# Mega2560_Grbl_to_RAMPS1-4_driver.net
KiCad netlist of a schematic drawn in EAGLE
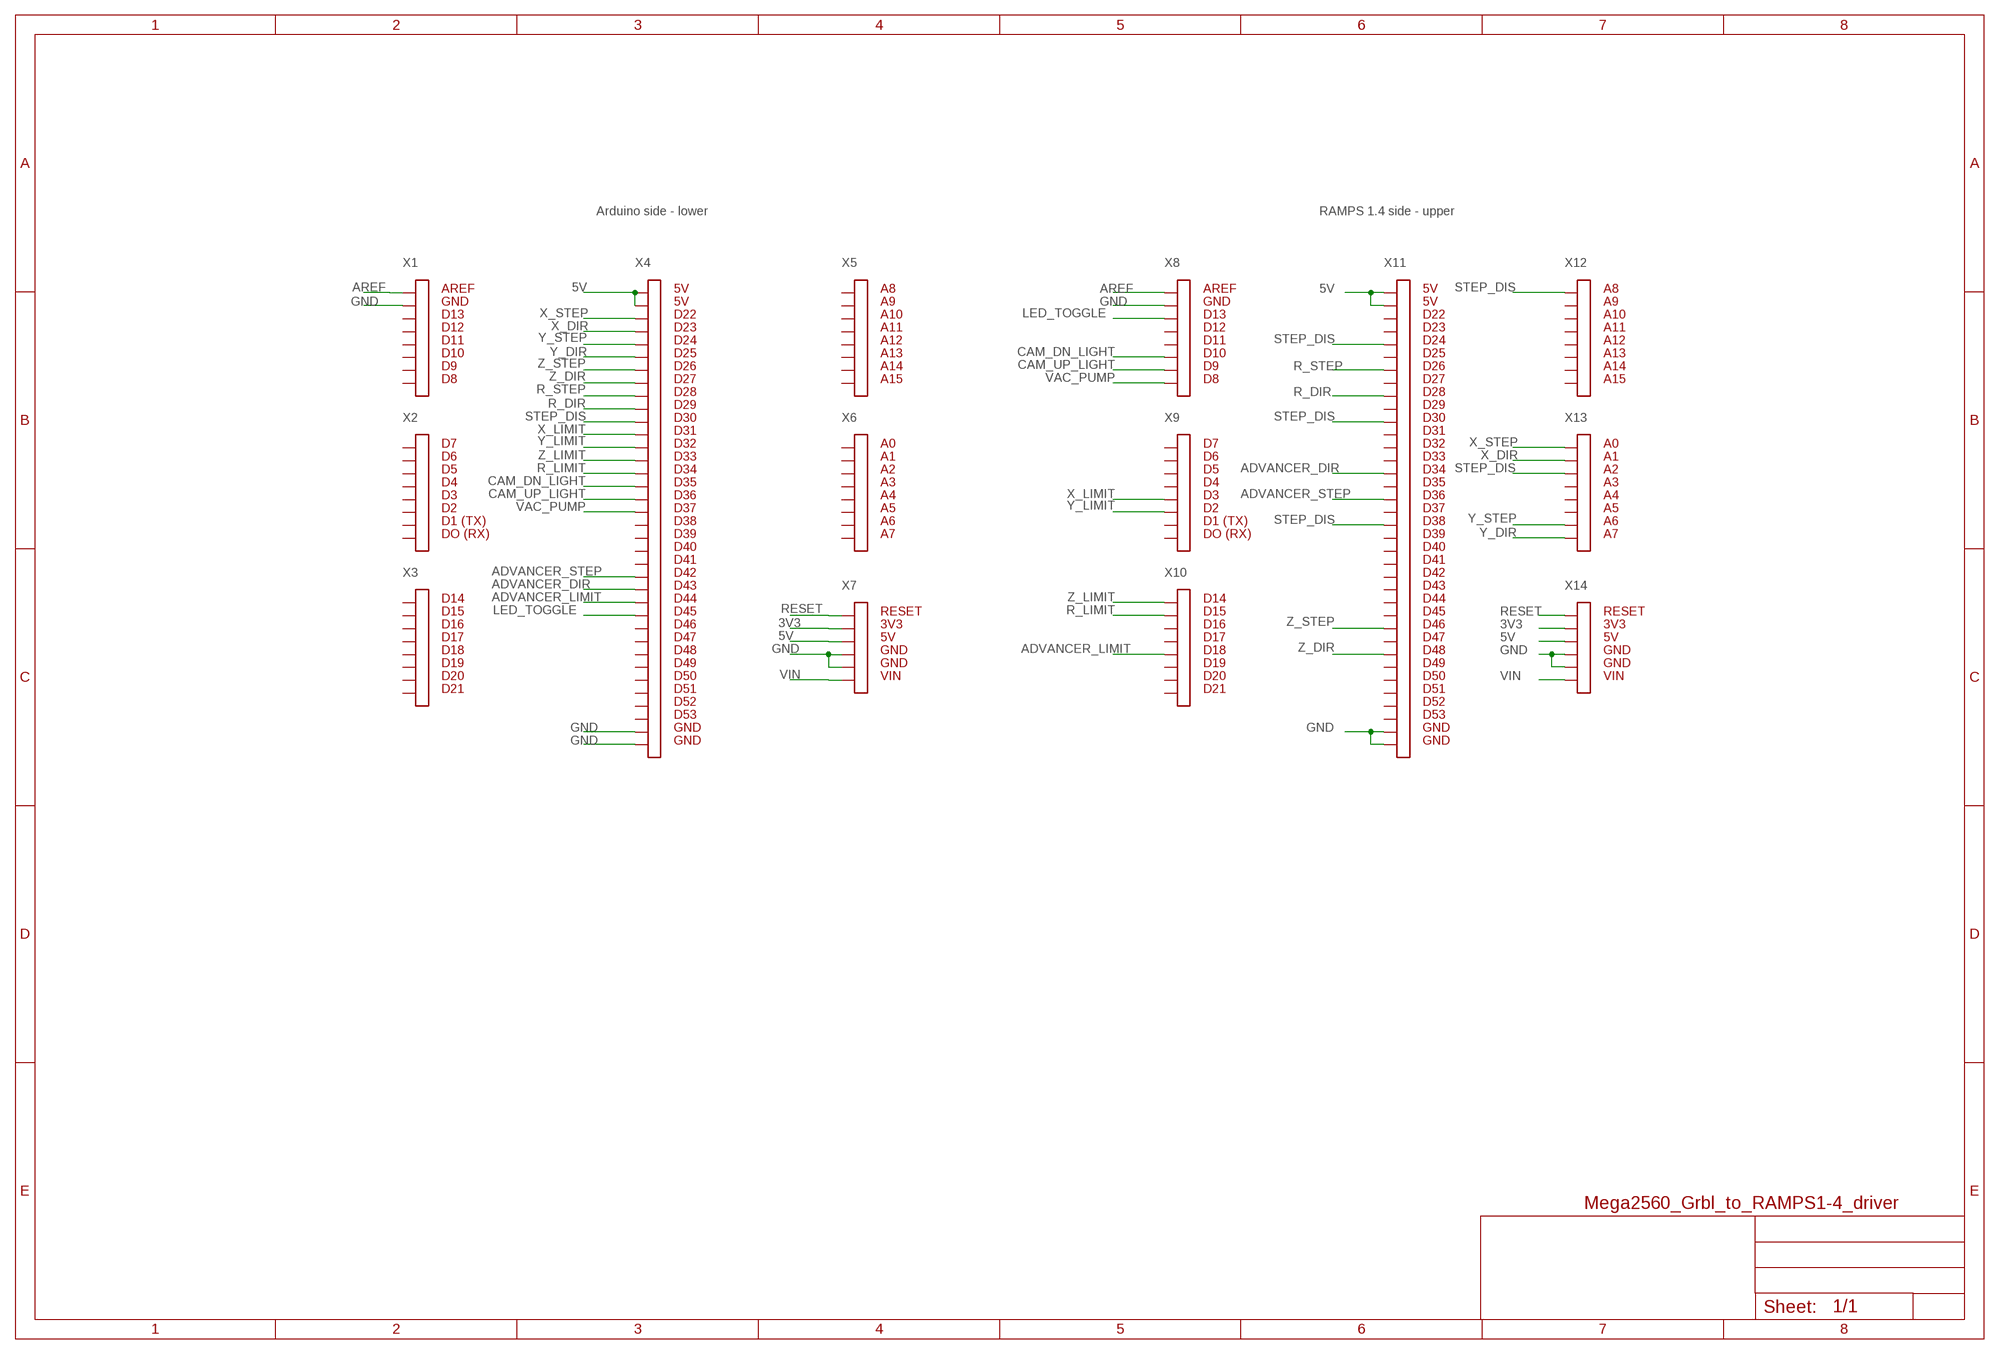
[diagram p0: schematic, sheet 1]

(export (version "E")
  (design (tool "Eeschema 10.0.6"))
  (components
    (comp (ref "X1")
      (value "M20-9770842")
      (footprint "eagle-import:8X1-P2.54-D1.00")
      (libsource (lib "eagle-import") (part "M20-9770842"))
    )
    (comp (ref "X2")
      (value "M20-9770842")
      (footprint "eagle-import:8X1-P2.54-D1.00")
      (libsource (lib "eagle-import") (part "M20-9770842"))
    )
    (comp (ref "X3")
      (value "M20-9770842")
      (footprint "eagle-import:8X1-P2.54-D1.00")
      (libsource (lib "eagle-import") (part "M20-9770842"))
    )
    (comp (ref "X4")
      (value "M20-9761842FLIP")
      (footprint "eagle-import:18X2-P2.54-D1.00")
      (libsource (lib "eagle-import") (part "M20-9761842FLIP"))
    )
    (comp (ref "X5")
      (value "M20-9770842")
      (footprint "eagle-import:8X1-P2.54-D1.00")
      (libsource (lib "eagle-import") (part "M20-9770842"))
    )
    (comp (ref "X6")
      (value "M20-9770842")
      (footprint "eagle-import:8X1-P2.54-D1.00")
      (libsource (lib "eagle-import") (part "M20-9770842"))
    )
    (comp (ref "X7")
      (value "M20-9770642")
      (footprint "eagle-import:6X1-P2.54-D1.00")
      (libsource (lib "eagle-import") (part "M20-9770642"))
    )
    (comp (ref "X8")
      (value "M20-7820842")
      (footprint "eagle-import:8X1-P2.54-D1.00")
      (libsource (lib "eagle-import") (part "M20-7820842"))
    )
    (comp (ref "X9")
      (value "M20-7820842")
      (footprint "eagle-import:8X1-P2.54-D1.00")
      (libsource (lib "eagle-import") (part "M20-7820842"))
    )
    (comp (ref "X10")
      (value "M20-7820842")
      (footprint "eagle-import:8X1-P2.54-D1.00")
      (libsource (lib "eagle-import") (part "M20-7820842"))
    )
    (comp (ref "X11")
      (value "M20-7831842")
      (footprint "eagle-import:18X2-P2.54-D1.00")
      (libsource (lib "eagle-import") (part "M20-7831842"))
    )
    (comp (ref "X12")
      (value "M20-7820842")
      (footprint "eagle-import:8X1-P2.54-D1.00")
      (libsource (lib "eagle-import") (part "M20-7820842"))
    )
    (comp (ref "X13")
      (value "M20-7820842")
      (footprint "eagle-import:8X1-P2.54-D1.00")
      (libsource (lib "eagle-import") (part "M20-7820842"))
    )
    (comp (ref "X14")
      (value "M20-7820642")
      (footprint "eagle-import:6X1-P2.54-D1.00")
      (libsource (lib "eagle-import") (part "M20-7820642"))
    )
  )
  (nets
    (net (code "1") (name "/3V3") (class "Default")
      (node (ref "X14") (pin "P$2") (pinfunction "P$2_P$2") (pintype "passive"))
      (node (ref "X7") (pin "P$2") (pinfunction "P$2_P$2") (pintype "passive"))
    )
    (net (code "2") (name "/5V") (class "Default")
      (node (ref "X11") (pin "P$1") (pinfunction "P$1_P$1") (pintype "passive"))
      (node (ref "X11") (pin "P$2") (pinfunction "P$2_P$2") (pintype "passive"))
      (node (ref "X14") (pin "P$3") (pinfunction "P$3_P$3") (pintype "passive"))
      (node (ref "X4") (pin "P$1") (pinfunction "P$2_P$1") (pintype "passive"))
      (node (ref "X4") (pin "P$2") (pinfunction "P$1_P$2") (pintype "passive"))
      (node (ref "X7") (pin "P$3") (pinfunction "P$3_P$3") (pintype "passive"))
    )
    (net (code "3") (name "/ADVANCER_DIR") (class "Default")
      (node (ref "X11") (pin "P$15") (pinfunction "P$15_P$15") (pintype "passive"))
      (node (ref "X4") (pin "P$23") (pinfunction "P$24_P$23") (pintype "passive"))
    )
    (net (code "4") (name "/ADVANCER_LIMIT") (class "Default")
      (node (ref "X10") (pin "P$5") (pinfunction "P$5_P$5") (pintype "passive"))
      (node (ref "X4") (pin "P$26") (pinfunction "P$25_P$26") (pintype "passive"))
    )
    (net (code "5") (name "/ADVANCER_STEP") (class "Default")
      (node (ref "X11") (pin "P$17") (pinfunction "P$17_P$17") (pintype "passive"))
      (node (ref "X4") (pin "P$24") (pinfunction "P$23_P$24") (pintype "passive"))
    )
    (net (code "6") (name "/AREF") (class "Default")
      (node (ref "X1") (pin "P$1") (pinfunction "P$1_P$1") (pintype "passive"))
      (node (ref "X8") (pin "P$1") (pinfunction "P$1_P$1") (pintype "passive"))
    )
    (net (code "7") (name "/CAM_DN_LIGHT") (class "Default")
      (node (ref "X4") (pin "P$15") (pinfunction "P$16_P$15") (pintype "passive"))
      (node (ref "X8") (pin "P$6") (pinfunction "P$6_P$6") (pintype "passive"))
    )
    (net (code "8") (name "/CAM_UP_LIGHT") (class "Default")
      (node (ref "X4") (pin "P$18") (pinfunction "P$17_P$18") (pintype "passive"))
      (node (ref "X8") (pin "P$7") (pinfunction "P$7_P$7") (pintype "passive"))
    )
    (net (code "9") (name "/GND") (class "Default")
      (node (ref "X1") (pin "P$2") (pinfunction "P$2_P$2") (pintype "passive"))
      (node (ref "X11") (pin "P$35") (pinfunction "P$35_P$35") (pintype "passive"))
      (node (ref "X11") (pin "P$36") (pinfunction "P$36_P$36") (pintype "passive"))
      (node (ref "X14") (pin "P$4") (pinfunction "P$4_P$4") (pintype "passive"))
      (node (ref "X14") (pin "P$5") (pinfunction "P$5_P$5") (pintype "passive"))
      (node (ref "X4") (pin "P$35") (pinfunction "P$36_P$35") (pintype "passive"))
      (node (ref "X4") (pin "P$36") (pinfunction "P$35_P$36") (pintype "passive"))
      (node (ref "X7") (pin "P$4") (pinfunction "P$4_P$4") (pintype "passive"))
      (node (ref "X7") (pin "P$5") (pinfunction "P$5_P$5") (pintype "passive"))
      (node (ref "X8") (pin "P$2") (pinfunction "P$2_P$2") (pintype "passive"))
    )
    (net (code "10") (name "/LED_TOGGLE") (class "Default")
      (node (ref "X4") (pin "P$25") (pinfunction "P$26_P$25") (pintype "passive"))
      (node (ref "X8") (pin "P$3") (pinfunction "P$3_P$3") (pintype "passive"))
    )
    (net (code "11") (name "/RESET") (class "Default")
      (node (ref "X14") (pin "P$1") (pinfunction "P$1_P$1") (pintype "passive"))
      (node (ref "X7") (pin "P$1") (pinfunction "P$1_P$1") (pintype "passive"))
    )
    (net (code "12") (name "/R_DIR") (class "Default")
      (node (ref "X11") (pin "P$9") (pinfunction "P$9_P$9") (pintype "passive"))
      (node (ref "X4") (pin "P$9") (pinfunction "P$10_P$9") (pintype "passive"))
    )
    (net (code "13") (name "/R_LIMIT") (class "Default")
      (node (ref "X10") (pin "P$2") (pinfunction "P$2_P$2") (pintype "passive"))
      (node (ref "X4") (pin "P$16") (pinfunction "P$15_P$16") (pintype "passive"))
    )
    (net (code "14") (name "/R_STEP") (class "Default")
      (node (ref "X11") (pin "P$7") (pinfunction "P$7_P$7") (pintype "passive"))
      (node (ref "X4") (pin "P$10") (pinfunction "P$9_P$10") (pintype "passive"))
    )
    (net (code "15") (name "/STEP_DIS") (class "Default")
      (node (ref "X11") (pin "P$11") (pinfunction "P$11_P$11") (pintype "passive"))
      (node (ref "X11") (pin "P$19") (pinfunction "P$19_P$19") (pintype "passive"))
      (node (ref "X11") (pin "P$5") (pinfunction "P$5_P$5") (pintype "passive"))
      (node (ref "X12") (pin "P$1") (pinfunction "P$1_P$1") (pintype "passive"))
      (node (ref "X13") (pin "P$3") (pinfunction "P$3_P$3") (pintype "passive"))
      (node (ref "X4") (pin "P$12") (pinfunction "P$11_P$12") (pintype "passive"))
    )
    (net (code "16") (name "/VAC_PUMP") (class "Default")
      (node (ref "X4") (pin "P$17") (pinfunction "P$18_P$17") (pintype "passive"))
      (node (ref "X8") (pin "P$8") (pinfunction "P$8_P$8") (pintype "passive"))
    )
    (net (code "17") (name "/VIN") (class "Default")
      (node (ref "X14") (pin "P$6") (pinfunction "P$6_P$6") (pintype "passive"))
      (node (ref "X7") (pin "P$6") (pinfunction "P$6_P$6") (pintype "passive"))
    )
    (net (code "18") (name "/X_DIR") (class "Default")
      (node (ref "X13") (pin "P$2") (pinfunction "P$2_P$2") (pintype "passive"))
      (node (ref "X4") (pin "P$3") (pinfunction "P$4_P$3") (pintype "passive"))
    )
    (net (code "19") (name "/X_LIMIT") (class "Default")
      (node (ref "X4") (pin "P$11") (pinfunction "P$12_P$11") (pintype "passive"))
      (node (ref "X9") (pin "P$5") (pinfunction "P$5_P$5") (pintype "passive"))
    )
    (net (code "20") (name "/X_STEP") (class "Default")
      (node (ref "X13") (pin "P$1") (pinfunction "P$1_P$1") (pintype "passive"))
      (node (ref "X4") (pin "P$4") (pinfunction "P$3_P$4") (pintype "passive"))
    )
    (net (code "21") (name "/Y_DIR") (class "Default")
      (node (ref "X13") (pin "P$8") (pinfunction "P$8_P$8") (pintype "passive"))
      (node (ref "X4") (pin "P$5") (pinfunction "P$6_P$5") (pintype "passive"))
    )
    (net (code "22") (name "/Y_LIMIT") (class "Default")
      (node (ref "X4") (pin "P$14") (pinfunction "P$13_P$14") (pintype "passive"))
      (node (ref "X9") (pin "P$6") (pinfunction "P$6_P$6") (pintype "passive"))
    )
    (net (code "23") (name "/Y_STEP") (class "Default")
      (node (ref "X13") (pin "P$7") (pinfunction "P$7_P$7") (pintype "passive"))
      (node (ref "X4") (pin "P$6") (pinfunction "P$5_P$6") (pintype "passive"))
    )
    (net (code "24") (name "/Z_DIR") (class "Default")
      (node (ref "X11") (pin "P$29") (pinfunction "P$29_P$29") (pintype "passive"))
      (node (ref "X4") (pin "P$7") (pinfunction "P$8_P$7") (pintype "passive"))
    )
    (net (code "25") (name "/Z_LIMIT") (class "Default")
      (node (ref "X10") (pin "P$1") (pinfunction "P$1_P$1") (pintype "passive"))
      (node (ref "X4") (pin "P$13") (pinfunction "P$14_P$13") (pintype "passive"))
    )
    (net (code "26") (name "/Z_STEP") (class "Default")
      (node (ref "X11") (pin "P$27") (pinfunction "P$27_P$27") (pintype "passive"))
      (node (ref "X4") (pin "P$8") (pinfunction "P$7_P$8") (pintype "passive"))
    )
    (net (code "27") (name "unconnected-(X1-PadP$3)") (class "Default")
      (node (ref "X1") (pin "P$3") (pinfunction "P$3_P$3") (pintype "passive"))
    )
    (net (code "28") (name "unconnected-(X1-PadP$4)") (class "Default")
      (node (ref "X1") (pin "P$4") (pinfunction "P$4_P$4") (pintype "passive"))
    )
    (net (code "29") (name "unconnected-(X1-PadP$5)") (class "Default")
      (node (ref "X1") (pin "P$5") (pinfunction "P$5_P$5") (pintype "passive"))
    )
    (net (code "30") (name "unconnected-(X1-PadP$6)") (class "Default")
      (node (ref "X1") (pin "P$6") (pinfunction "P$6_P$6") (pintype "passive"))
    )
    (net (code "31") (name "unconnected-(X1-PadP$7)") (class "Default")
      (node (ref "X1") (pin "P$7") (pinfunction "P$7_P$7") (pintype "passive"))
    )
    (net (code "32") (name "unconnected-(X1-PadP$8)") (class "Default")
      (node (ref "X1") (pin "P$8") (pinfunction "P$8_P$8") (pintype "passive"))
    )
    (net (code "33") (name "unconnected-(X2-PadP$1)") (class "Default")
      (node (ref "X2") (pin "P$1") (pinfunction "P$1_P$1") (pintype "passive"))
    )
    (net (code "34") (name "unconnected-(X2-PadP$2)") (class "Default")
      (node (ref "X2") (pin "P$2") (pinfunction "P$2_P$2") (pintype "passive"))
    )
    (net (code "35") (name "unconnected-(X2-PadP$3)") (class "Default")
      (node (ref "X2") (pin "P$3") (pinfunction "P$3_P$3") (pintype "passive"))
    )
    (net (code "36") (name "unconnected-(X2-PadP$4)") (class "Default")
      (node (ref "X2") (pin "P$4") (pinfunction "P$4_P$4") (pintype "passive"))
    )
    (net (code "37") (name "unconnected-(X2-PadP$5)") (class "Default")
      (node (ref "X2") (pin "P$5") (pinfunction "P$5_P$5") (pintype "passive"))
    )
    (net (code "38") (name "unconnected-(X2-PadP$6)") (class "Default")
      (node (ref "X2") (pin "P$6") (pinfunction "P$6_P$6") (pintype "passive"))
    )
    (net (code "39") (name "unconnected-(X2-PadP$7)") (class "Default")
      (node (ref "X2") (pin "P$7") (pinfunction "P$7_P$7") (pintype "passive"))
    )
    (net (code "40") (name "unconnected-(X2-PadP$8)") (class "Default")
      (node (ref "X2") (pin "P$8") (pinfunction "P$8_P$8") (pintype "passive"))
    )
    (net (code "41") (name "unconnected-(X3-PadP$1)") (class "Default")
      (node (ref "X3") (pin "P$1") (pinfunction "P$1_P$1") (pintype "passive"))
    )
    (net (code "42") (name "unconnected-(X3-PadP$2)") (class "Default")
      (node (ref "X3") (pin "P$2") (pinfunction "P$2_P$2") (pintype "passive"))
    )
    (net (code "43") (name "unconnected-(X3-PadP$3)") (class "Default")
      (node (ref "X3") (pin "P$3") (pinfunction "P$3_P$3") (pintype "passive"))
    )
    (net (code "44") (name "unconnected-(X3-PadP$4)") (class "Default")
      (node (ref "X3") (pin "P$4") (pinfunction "P$4_P$4") (pintype "passive"))
    )
    (net (code "45") (name "unconnected-(X3-PadP$5)") (class "Default")
      (node (ref "X3") (pin "P$5") (pinfunction "P$5_P$5") (pintype "passive"))
    )
    (net (code "46") (name "unconnected-(X3-PadP$6)") (class "Default")
      (node (ref "X3") (pin "P$6") (pinfunction "P$6_P$6") (pintype "passive"))
    )
    (net (code "47") (name "unconnected-(X3-PadP$7)") (class "Default")
      (node (ref "X3") (pin "P$7") (pinfunction "P$7_P$7") (pintype "passive"))
    )
    (net (code "48") (name "unconnected-(X3-PadP$8)") (class "Default")
      (node (ref "X3") (pin "P$8") (pinfunction "P$8_P$8") (pintype "passive"))
    )
    (net (code "49") (name "unconnected-(X4-P$19-PadP$20)") (class "Default")
      (node (ref "X4") (pin "P$20") (pinfunction "P$19_P$20") (pintype "passive"))
    )
    (net (code "50") (name "unconnected-(X4-P$20-PadP$19)") (class "Default")
      (node (ref "X4") (pin "P$19") (pinfunction "P$20_P$19") (pintype "passive"))
    )
    (net (code "51") (name "unconnected-(X4-P$21-PadP$22)") (class "Default")
      (node (ref "X4") (pin "P$22") (pinfunction "P$21_P$22") (pintype "passive"))
    )
    (net (code "52") (name "unconnected-(X4-P$22-PadP$21)") (class "Default")
      (node (ref "X4") (pin "P$21") (pinfunction "P$22_P$21") (pintype "passive"))
    )
    (net (code "53") (name "unconnected-(X4-P$27-PadP$28)") (class "Default")
      (node (ref "X4") (pin "P$28") (pinfunction "P$27_P$28") (pintype "passive"))
    )
    (net (code "54") (name "unconnected-(X4-P$28-PadP$27)") (class "Default")
      (node (ref "X4") (pin "P$27") (pinfunction "P$28_P$27") (pintype "passive"))
    )
    (net (code "55") (name "unconnected-(X4-P$29-PadP$30)") (class "Default")
      (node (ref "X4") (pin "P$30") (pinfunction "P$29_P$30") (pintype "passive"))
    )
    (net (code "56") (name "unconnected-(X4-P$30-PadP$29)") (class "Default")
      (node (ref "X4") (pin "P$29") (pinfunction "P$30_P$29") (pintype "passive"))
    )
    (net (code "57") (name "unconnected-(X4-P$31-PadP$32)") (class "Default")
      (node (ref "X4") (pin "P$32") (pinfunction "P$31_P$32") (pintype "passive"))
    )
    (net (code "58") (name "unconnected-(X4-P$32-PadP$31)") (class "Default")
      (node (ref "X4") (pin "P$31") (pinfunction "P$32_P$31") (pintype "passive"))
    )
    (net (code "59") (name "unconnected-(X4-P$33-PadP$34)") (class "Default")
      (node (ref "X4") (pin "P$34") (pinfunction "P$33_P$34") (pintype "passive"))
    )
    (net (code "60") (name "unconnected-(X4-P$34-PadP$33)") (class "Default")
      (node (ref "X4") (pin "P$33") (pinfunction "P$34_P$33") (pintype "passive"))
    )
    (net (code "61") (name "unconnected-(X5-PadP$1)") (class "Default")
      (node (ref "X5") (pin "P$1") (pinfunction "P$1_P$1") (pintype "passive"))
    )
    (net (code "62") (name "unconnected-(X5-PadP$2)") (class "Default")
      (node (ref "X5") (pin "P$2") (pinfunction "P$2_P$2") (pintype "passive"))
    )
    (net (code "63") (name "unconnected-(X5-PadP$3)") (class "Default")
      (node (ref "X5") (pin "P$3") (pinfunction "P$3_P$3") (pintype "passive"))
    )
    (net (code "64") (name "unconnected-(X5-PadP$4)") (class "Default")
      (node (ref "X5") (pin "P$4") (pinfunction "P$4_P$4") (pintype "passive"))
    )
    (net (code "65") (name "unconnected-(X5-PadP$5)") (class "Default")
      (node (ref "X5") (pin "P$5") (pinfunction "P$5_P$5") (pintype "passive"))
    )
    (net (code "66") (name "unconnected-(X5-PadP$6)") (class "Default")
      (node (ref "X5") (pin "P$6") (pinfunction "P$6_P$6") (pintype "passive"))
    )
    (net (code "67") (name "unconnected-(X5-PadP$7)") (class "Default")
      (node (ref "X5") (pin "P$7") (pinfunction "P$7_P$7") (pintype "passive"))
    )
    (net (code "68") (name "unconnected-(X5-PadP$8)") (class "Default")
      (node (ref "X5") (pin "P$8") (pinfunction "P$8_P$8") (pintype "passive"))
    )
    (net (code "69") (name "unconnected-(X6-PadP$1)") (class "Default")
      (node (ref "X6") (pin "P$1") (pinfunction "P$1_P$1") (pintype "passive"))
    )
    (net (code "70") (name "unconnected-(X6-PadP$2)") (class "Default")
      (node (ref "X6") (pin "P$2") (pinfunction "P$2_P$2") (pintype "passive"))
    )
    (net (code "71") (name "unconnected-(X6-PadP$3)") (class "Default")
      (node (ref "X6") (pin "P$3") (pinfunction "P$3_P$3") (pintype "passive"))
    )
    (net (code "72") (name "unconnected-(X6-PadP$4)") (class "Default")
      (node (ref "X6") (pin "P$4") (pinfunction "P$4_P$4") (pintype "passive"))
    )
    (net (code "73") (name "unconnected-(X6-PadP$5)") (class "Default")
      (node (ref "X6") (pin "P$5") (pinfunction "P$5_P$5") (pintype "passive"))
    )
    (net (code "74") (name "unconnected-(X6-PadP$6)") (class "Default")
      (node (ref "X6") (pin "P$6") (pinfunction "P$6_P$6") (pintype "passive"))
    )
    (net (code "75") (name "unconnected-(X6-PadP$7)") (class "Default")
      (node (ref "X6") (pin "P$7") (pinfunction "P$7_P$7") (pintype "passive"))
    )
    (net (code "76") (name "unconnected-(X6-PadP$8)") (class "Default")
      (node (ref "X6") (pin "P$8") (pinfunction "P$8_P$8") (pintype "passive"))
    )
    (net (code "77") (name "unconnected-(X8-PadP$4)") (class "Default")
      (node (ref "X8") (pin "P$4") (pinfunction "P$4_P$4") (pintype "passive"))
    )
    (net (code "78") (name "unconnected-(X8-PadP$5)") (class "Default")
      (node (ref "X8") (pin "P$5") (pinfunction "P$5_P$5") (pintype "passive"))
    )
    (net (code "79") (name "unconnected-(X9-PadP$1)") (class "Default")
      (node (ref "X9") (pin "P$1") (pinfunction "P$1_P$1") (pintype "passive"))
    )
    (net (code "80") (name "unconnected-(X9-PadP$2)") (class "Default")
      (node (ref "X9") (pin "P$2") (pinfunction "P$2_P$2") (pintype "passive"))
    )
    (net (code "81") (name "unconnected-(X9-PadP$3)") (class "Default")
      (node (ref "X9") (pin "P$3") (pinfunction "P$3_P$3") (pintype "passive"))
    )
    (net (code "82") (name "unconnected-(X9-PadP$4)") (class "Default")
      (node (ref "X9") (pin "P$4") (pinfunction "P$4_P$4") (pintype "passive"))
    )
    (net (code "83") (name "unconnected-(X9-PadP$7)") (class "Default")
      (node (ref "X9") (pin "P$7") (pinfunction "P$7_P$7") (pintype "passive"))
    )
    (net (code "84") (name "unconnected-(X9-PadP$8)") (class "Default")
      (node (ref "X9") (pin "P$8") (pinfunction "P$8_P$8") (pintype "passive"))
    )
    (net (code "85") (name "unconnected-(X10-PadP$3)") (class "Default")
      (node (ref "X10") (pin "P$3") (pinfunction "P$3_P$3") (pintype "passive"))
    )
    (net (code "86") (name "unconnected-(X10-PadP$4)") (class "Default")
      (node (ref "X10") (pin "P$4") (pinfunction "P$4_P$4") (pintype "passive"))
    )
    (net (code "87") (name "unconnected-(X10-PadP$6)") (class "Default")
      (node (ref "X10") (pin "P$6") (pinfunction "P$6_P$6") (pintype "passive"))
    )
    (net (code "88") (name "unconnected-(X10-PadP$7)") (class "Default")
      (node (ref "X10") (pin "P$7") (pinfunction "P$7_P$7") (pintype "passive"))
    )
    (net (code "89") (name "unconnected-(X10-PadP$8)") (class "Default")
      (node (ref "X10") (pin "P$8") (pinfunction "P$8_P$8") (pintype "passive"))
    )
    (net (code "90") (name "unconnected-(X11-PadP$3)") (class "Default")
      (node (ref "X11") (pin "P$3") (pinfunction "P$3_P$3") (pintype "passive"))
    )
    (net (code "91") (name "unconnected-(X11-PadP$4)") (class "Default")
      (node (ref "X11") (pin "P$4") (pinfunction "P$4_P$4") (pintype "passive"))
    )
    (net (code "92") (name "unconnected-(X11-PadP$6)") (class "Default")
      (node (ref "X11") (pin "P$6") (pinfunction "P$6_P$6") (pintype "passive"))
    )
    (net (code "93") (name "unconnected-(X11-PadP$8)") (class "Default")
      (node (ref "X11") (pin "P$8") (pinfunction "P$8_P$8") (pintype "passive"))
    )
    (net (code "94") (name "unconnected-(X11-PadP$10)") (class "Default")
      (node (ref "X11") (pin "P$10") (pinfunction "P$10_P$10") (pintype "passive"))
    )
    (net (code "95") (name "unconnected-(X11-PadP$12)") (class "Default")
      (node (ref "X11") (pin "P$12") (pinfunction "P$12_P$12") (pintype "passive"))
    )
    (net (code "96") (name "unconnected-(X11-PadP$13)") (class "Default")
      (node (ref "X11") (pin "P$13") (pinfunction "P$13_P$13") (pintype "passive"))
    )
    (net (code "97") (name "unconnected-(X11-PadP$14)") (class "Default")
      (node (ref "X11") (pin "P$14") (pinfunction "P$14_P$14") (pintype "passive"))
    )
    (net (code "98") (name "unconnected-(X11-PadP$16)") (class "Default")
      (node (ref "X11") (pin "P$16") (pinfunction "P$16_P$16") (pintype "passive"))
    )
    (net (code "99") (name "unconnected-(X11-PadP$18)") (class "Default")
      (node (ref "X11") (pin "P$18") (pinfunction "P$18_P$18") (pintype "passive"))
    )
    (net (code "100") (name "unconnected-(X11-PadP$20)") (class "Default")
      (node (ref "X11") (pin "P$20") (pinfunction "P$20_P$20") (pintype "passive"))
    )
    (net (code "101") (name "unconnected-(X11-PadP$21)") (class "Default")
      (node (ref "X11") (pin "P$21") (pinfunction "P$21_P$21") (pintype "passive"))
    )
    (net (code "102") (name "unconnected-(X11-PadP$22)") (class "Default")
      (node (ref "X11") (pin "P$22") (pinfunction "P$22_P$22") (pintype "passive"))
    )
    (net (code "103") (name "unconnected-(X11-PadP$23)") (class "Default")
      (node (ref "X11") (pin "P$23") (pinfunction "P$23_P$23") (pintype "passive"))
    )
    (net (code "104") (name "unconnected-(X11-PadP$24)") (class "Default")
      (node (ref "X11") (pin "P$24") (pinfunction "P$24_P$24") (pintype "passive"))
    )
    (net (code "105") (name "unconnected-(X11-PadP$25)") (class "Default")
      (node (ref "X11") (pin "P$25") (pinfunction "P$25_P$25") (pintype "passive"))
    )
    (net (code "106") (name "unconnected-(X11-PadP$26)") (class "Default")
      (node (ref "X11") (pin "P$26") (pinfunction "P$26_P$26") (pintype "passive"))
    )
    (net (code "107") (name "unconnected-(X11-PadP$28)") (class "Default")
      (node (ref "X11") (pin "P$28") (pinfunction "P$28_P$28") (pintype "passive"))
    )
    (net (code "108") (name "unconnected-(X11-PadP$30)") (class "Default")
      (node (ref "X11") (pin "P$30") (pinfunction "P$30_P$30") (pintype "passive"))
    )
    (net (code "109") (name "unconnected-(X11-PadP$31)") (class "Default")
      (node (ref "X11") (pin "P$31") (pinfunction "P$31_P$31") (pintype "passive"))
    )
    (net (code "110") (name "unconnected-(X11-PadP$32)") (class "Default")
      (node (ref "X11") (pin "P$32") (pinfunction "P$32_P$32") (pintype "passive"))
    )
    (net (code "111") (name "unconnected-(X11-PadP$33)") (class "Default")
      (node (ref "X11") (pin "P$33") (pinfunction "P$33_P$33") (pintype "passive"))
    )
    (net (code "112") (name "unconnected-(X11-PadP$34)") (class "Default")
      (node (ref "X11") (pin "P$34") (pinfunction "P$34_P$34") (pintype "passive"))
    )
    (net (code "113") (name "unconnected-(X12-PadP$2)") (class "Default")
      (node (ref "X12") (pin "P$2") (pinfunction "P$2_P$2") (pintype "passive"))
    )
    (net (code "114") (name "unconnected-(X12-PadP$3)") (class "Default")
      (node (ref "X12") (pin "P$3") (pinfunction "P$3_P$3") (pintype "passive"))
    )
    (net (code "115") (name "unconnected-(X12-PadP$4)") (class "Default")
      (node (ref "X12") (pin "P$4") (pinfunction "P$4_P$4") (pintype "passive"))
    )
    (net (code "116") (name "unconnected-(X12-PadP$5)") (class "Default")
      (node (ref "X12") (pin "P$5") (pinfunction "P$5_P$5") (pintype "passive"))
    )
    (net (code "117") (name "unconnected-(X12-PadP$6)") (class "Default")
      (node (ref "X12") (pin "P$6") (pinfunction "P$6_P$6") (pintype "passive"))
    )
    (net (code "118") (name "unconnected-(X12-PadP$7)") (class "Default")
      (node (ref "X12") (pin "P$7") (pinfunction "P$7_P$7") (pintype "passive"))
    )
    (net (code "119") (name "unconnected-(X12-PadP$8)") (class "Default")
      (node (ref "X12") (pin "P$8") (pinfunction "P$8_P$8") (pintype "passive"))
    )
    (net (code "120") (name "unconnected-(X13-PadP$4)") (class "Default")
      (node (ref "X13") (pin "P$4") (pinfunction "P$4_P$4") (pintype "passive"))
    )
    (net (code "121") (name "unconnected-(X13-PadP$5)") (class "Default")
      (node (ref "X13") (pin "P$5") (pinfunction "P$5_P$5") (pintype "passive"))
    )
    (net (code "122") (name "unconnected-(X13-PadP$6)") (class "Default")
      (node (ref "X13") (pin "P$6") (pinfunction "P$6_P$6") (pintype "passive"))
    )
  )
)
